# Breakout.net
KiCad netlist of a schematic drawn in EAGLE
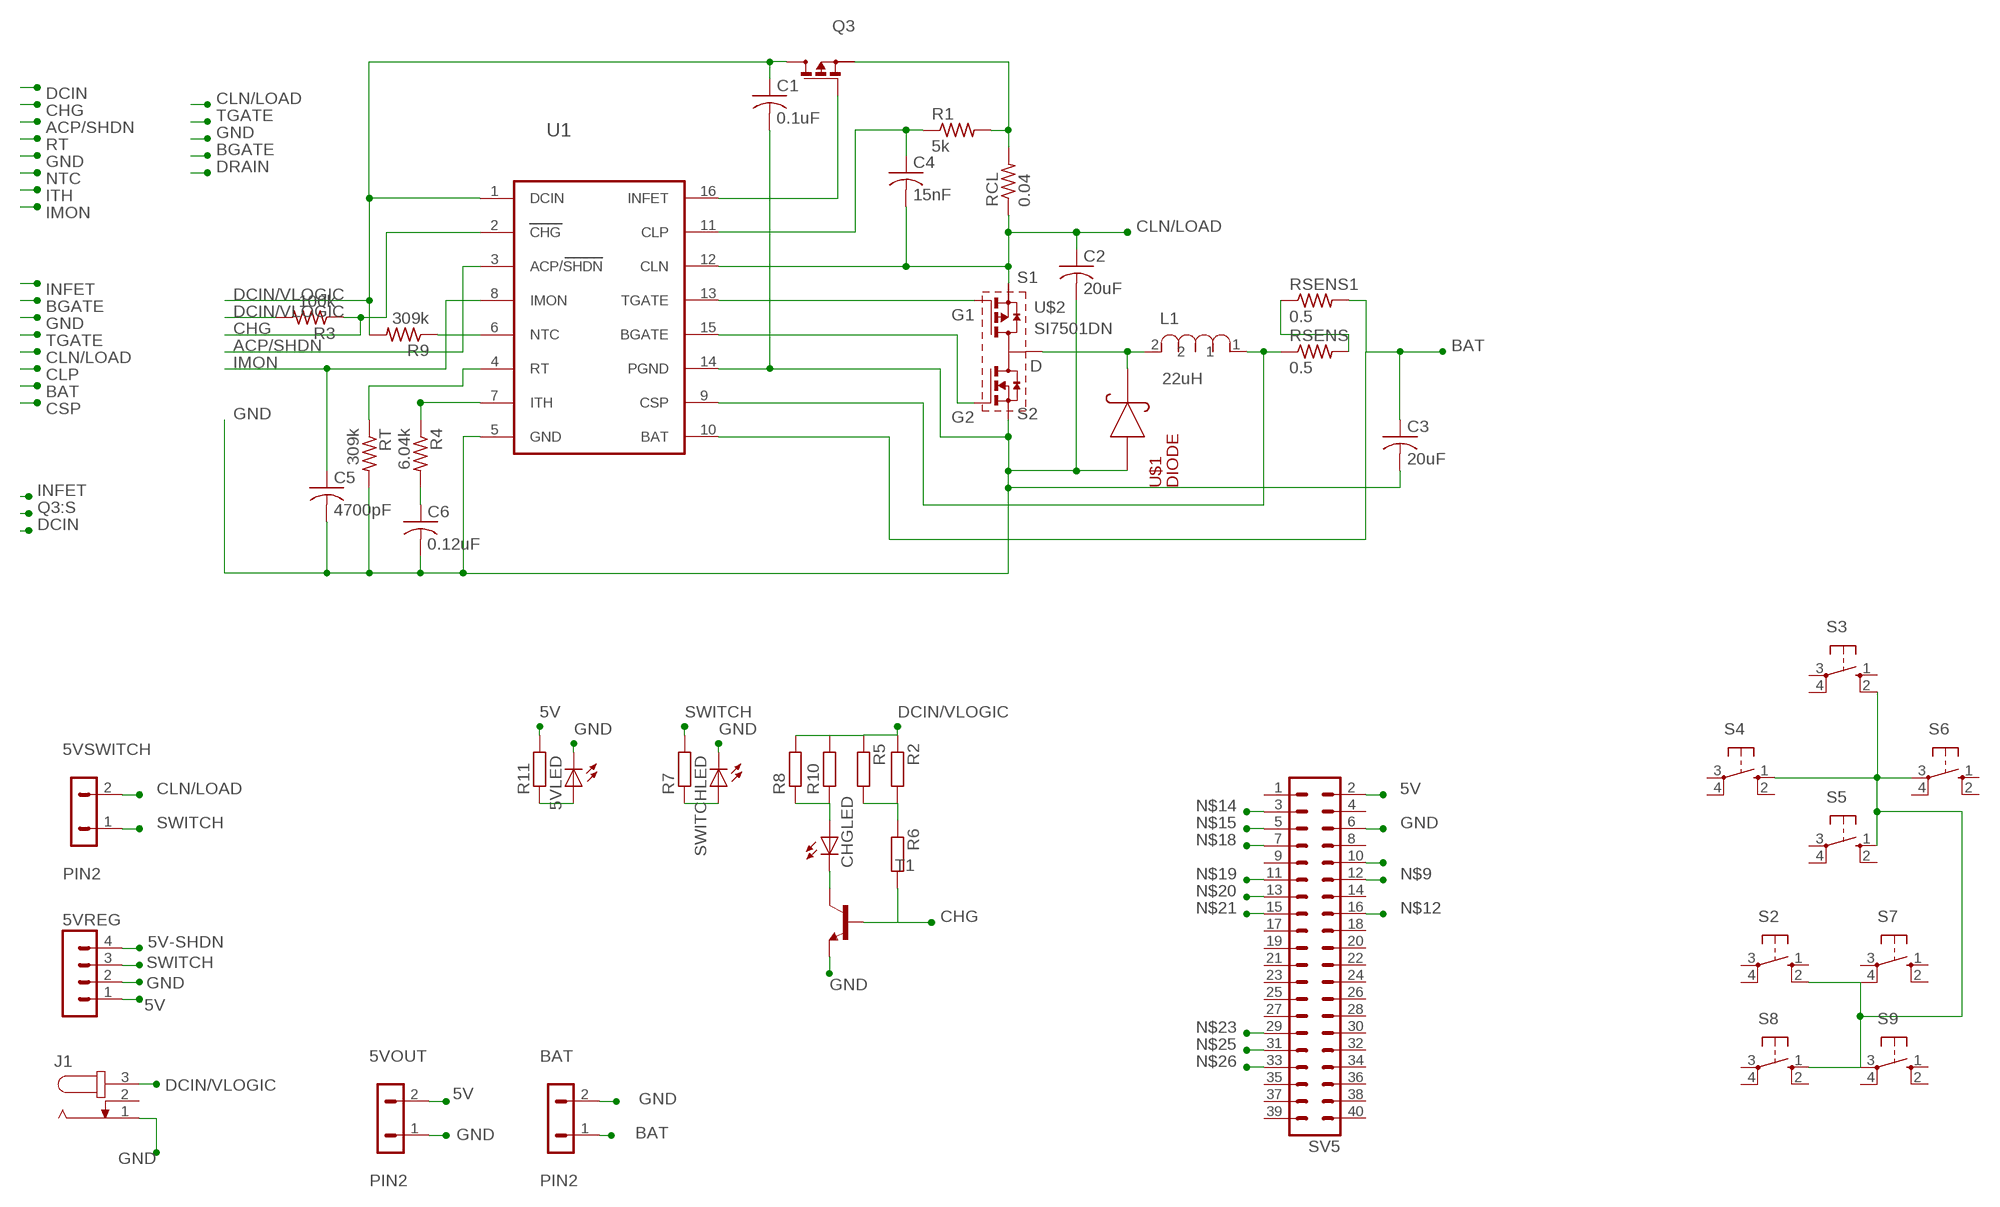
[diagram p0: schematic, sheet 1]

(export (version "E")
  (design (tool "Eeschema 10.0.6"))
  (components
    (comp (ref "5VLED")
      (value "LED5MM")
      (footprint "eagle-import:LED5MM")
      (libsource (lib "eagle-import") (part "LED5MM"))
    )
    (comp (ref "5VOUT")
      (value "PIN2")
      (footprint "eagle-import:PIN2")
      (libsource (lib "eagle-import") (part "PIN2"))
    )
    (comp (ref "5VREG")
      (value "MA04-1")
      (footprint "eagle-import:MA04-1")
      (libsource (lib "eagle-import") (part "MA04-1"))
    )
    (comp (ref "5VSWITCH")
      (value "PIN2")
      (footprint "eagle-import:PIN2")
      (libsource (lib "eagle-import") (part "PIN2"))
    )
    (comp (ref "BAT")
      (value "PIN2")
      (footprint "eagle-import:PIN2")
      (libsource (lib "eagle-import") (part "PIN2"))
    )
    (comp (ref "C1")
      (value "0.1uF")
      (footprint "eagle-import:C1210")
      (libsource (lib "eagle-import") (part "C-USC1210"))
    )
    (comp (ref "C2")
      (value "20uF")
      (footprint "eagle-import:C1210")
      (libsource (lib "eagle-import") (part "C-USC1210"))
    )
    (comp (ref "C3")
      (value "20uF")
      (footprint "eagle-import:C1210")
      (libsource (lib "eagle-import") (part "C-USC1210"))
    )
    (comp (ref "C4")
      (value "15nF")
      (footprint "eagle-import:C1210")
      (libsource (lib "eagle-import") (part "C-USC1210"))
    )
    (comp (ref "C5")
      (value "4700pF")
      (footprint "eagle-import:C1210")
      (libsource (lib "eagle-import") (part "C-USC1210"))
    )
    (comp (ref "C6")
      (value "0.12uF")
      (footprint "eagle-import:C1210")
      (libsource (lib "eagle-import") (part "C-USC1210"))
    )
    (comp (ref "CHGLED")
      (value "LED5MM")
      (footprint "eagle-import:LED5MM")
      (libsource (lib "eagle-import") (part "LED5MM"))
    )
    (comp (ref "J1")
      (value "JACK-PLUG0")
      (footprint "eagle-import:SPC4077")
      (libsource (lib "eagle-import") (part "JACK-PLUG0"))
    )
    (comp (ref "L1")
      (value "22uH")
      (footprint "eagle-import:POWERINDUCTOR")
      (libsource (lib "eagle-import") (part "SDR1005INDUCTOR"))
    )
    (comp (ref "Q3")
      (value "MOSFET")
      (footprint "eagle-import:SOT-23")
      (libsource (lib "eagle-import") (part "MOSFET"))
    )
    (comp (ref "R1")
      (value "5k")
      (footprint "eagle-import:R1206")
      (libsource (lib "eagle-import") (part "R-US_R1206"))
    )
    (comp (ref "R2")
      (value "R-EU_0207/7")
      (footprint "eagle-import:0207_7")
      (libsource (lib "eagle-import") (part "R-EU_0207/7"))
    )
    (comp (ref "R3")
      (value "100k")
      (footprint "eagle-import:R1206")
      (libsource (lib "eagle-import") (part "R-US_R1206"))
    )
    (comp (ref "R4")
      (value "6.04k")
      (footprint "eagle-import:R1206")
      (libsource (lib "eagle-import") (part "R-US_R1206"))
    )
    (comp (ref "R5")
      (value "R-EU_0207/7")
      (footprint "eagle-import:0207_7")
      (libsource (lib "eagle-import") (part "R-EU_0207/7"))
    )
    (comp (ref "R6")
      (value "R-EU_0207/7")
      (footprint "eagle-import:0207_7")
      (libsource (lib "eagle-import") (part "R-EU_0207/7"))
    )
    (comp (ref "R7")
      (value "R-EU_0207/7")
      (footprint "eagle-import:0207_7")
      (libsource (lib "eagle-import") (part "R-EU_0207/7"))
    )
    (comp (ref "R8")
      (value "R-EU_0207/7")
      (footprint "eagle-import:0207_7")
      (libsource (lib "eagle-import") (part "R-EU_0207/7"))
    )
    (comp (ref "R9")
      (value "309k")
      (footprint "eagle-import:R1206")
      (libsource (lib "eagle-import") (part "R-US_R1206"))
    )
    (comp (ref "R10")
      (value "R-EU_0207/7")
      (footprint "eagle-import:0207_7")
      (libsource (lib "eagle-import") (part "R-EU_0207/7"))
    )
    (comp (ref "R11")
      (value "R-EU_0207/7")
      (footprint "eagle-import:0207_7")
      (libsource (lib "eagle-import") (part "R-EU_0207/7"))
    )
    (comp (ref "RCL")
      (value "0.04")
      (footprint "eagle-import:R1206")
      (libsource (lib "eagle-import") (part "R-US_R1206"))
    )
    (comp (ref "RSENS")
      (value "0.5")
      (footprint "eagle-import:0612_1632")
      (libsource (lib "eagle-import") (part "0612/1632"))
    )
    (comp (ref "RSENS1")
      (value "0.5")
      (footprint "eagle-import:0612_1632")
      (libsource (lib "eagle-import") (part "0612/1632"))
    )
    (comp (ref "RT")
      (value "309k")
      (footprint "eagle-import:R1206")
      (libsource (lib "eagle-import") (part "R-US_R1206"))
    )
    (comp (ref "S2")
      (value "10-XX")
      (footprint "eagle-import:B3F-10XX")
      (fields (field (name "MPN") "B3F-1000"))
      (libsource (lib "eagle-import") (part "10-XX"))
    )
    (comp (ref "S3")
      (value "10-XX")
      (footprint "eagle-import:B3F-10XX")
      (fields (field (name "MPN") "B3F-1000"))
      (libsource (lib "eagle-import") (part "10-XX"))
    )
    (comp (ref "S4")
      (value "10-XX")
      (footprint "eagle-import:B3F-10XX")
      (fields (field (name "MPN") "B3F-1000"))
      (libsource (lib "eagle-import") (part "10-XX"))
    )
    (comp (ref "S5")
      (value "10-XX")
      (footprint "eagle-import:B3F-10XX")
      (fields (field (name "MPN") "B3F-1000"))
      (libsource (lib "eagle-import") (part "10-XX"))
    )
    (comp (ref "S6")
      (value "10-XX")
      (footprint "eagle-import:B3F-10XX")
      (fields (field (name "MPN") "B3F-1000"))
      (libsource (lib "eagle-import") (part "10-XX"))
    )
    (comp (ref "S7")
      (value "10-XX")
      (footprint "eagle-import:B3F-10XX")
      (fields (field (name "MPN") "B3F-1000"))
      (libsource (lib "eagle-import") (part "10-XX"))
    )
    (comp (ref "S8")
      (value "10-XX")
      (footprint "eagle-import:B3F-10XX")
      (fields (field (name "MPN") "B3F-1000"))
      (libsource (lib "eagle-import") (part "10-XX"))
    )
    (comp (ref "S9")
      (value "10-XX")
      (footprint "eagle-import:B3F-10XX")
      (fields (field (name "MPN") "B3F-1000"))
      (libsource (lib "eagle-import") (part "10-XX"))
    )
    (comp (ref "SV5")
      (value "MA20-2")
      (footprint "eagle-import:MA20-2")
      (libsource (lib "eagle-import") (part "MA20-2"))
    )
    (comp (ref "SWITCHLED")
      (value "LED5MM")
      (footprint "eagle-import:LED5MM")
      (libsource (lib "eagle-import") (part "LED5MM"))
    )
    (comp (ref "T1")
      (value "-NPN-TO92-E1")
      (footprint "eagle-import:TO92-E1")
      (libsource (lib "eagle-import") (part "-NPN-TO92-E1"))
    )
    (comp (ref "U$1")
      (value "DIODE")
      (footprint "eagle-import:DIODE")
      (libsource (lib "eagle-import") (part "DIODE"))
    )
    (comp (ref "U$2")
      (value "SI7501DN")
      (footprint "eagle-import:POWERPAK")
      (libsource (lib "eagle-import") (part "SI7501DN"))
    )
    (comp (ref "U1")
      (value "LTC6004")
      (footprint "eagle-import:SSOP-16")
      (libsource (lib "eagle-import") (part "LTC6004"))
    )
  )
  (nets
    (net (code "1") (name "/5V") (class "Default")
      (node (ref "5VOUT") (pin "2") (pinfunction "2_2") (pintype "passive"))
      (node (ref "5VREG") (pin "1") (pinfunction "1_1") (pintype "passive"))
      (node (ref "R11") (pin "2") (pinfunction "2_2") (pintype "passive"))
      (node (ref "SV5") (pin "2") (pinfunction "2_2") (pintype "passive"))
    )
    (net (code "2") (name "/5V-SHDN") (class "Default")
      (node (ref "5VREG") (pin "4") (pinfunction "4_4") (pintype "passive"))
    )
    (net (code "3") (name "/ACP{slash}SHDN") (class "Default")
      (node (ref "U1") (pin "3") (pinfunction "ACP/SHDN_3") (pintype "power_in"))
    )
    (net (code "4") (name "/BAT") (class "Default")
      (node (ref "BAT") (pin "1") (pinfunction "1_1") (pintype "passive"))
      (node (ref "C3") (pin "1") (pinfunction "1_1") (pintype "passive"))
      (node (ref "RSENS1") (pin "2") (pinfunction "2_2") (pintype "passive"))
      (node (ref "U1") (pin "10") (pinfunction "BAT_10") (pintype "power_in"))
    )
    (net (code "5") (name "/BGATE") (class "Default")
      (node (ref "U$2") (pin "G2") (pinfunction "G2_G2") (pintype "passive"))
      (node (ref "U1") (pin "15") (pinfunction "BGATE_15") (pintype "power_in"))
    )
    (net (code "6") (name "/CHG") (class "Default")
      (node (ref "R3") (pin "1") (pinfunction "1_1") (pintype "passive"))
      (node (ref "R6") (pin "2") (pinfunction "2_2") (pintype "passive"))
      (node (ref "T1") (pin "2") (pinfunction "B_2") (pintype "passive"))
      (node (ref "U1") (pin "2") (pinfunction "CHG_2") (pintype "power_in"))
    )
    (net (code "7") (name "/CLN{slash}LOAD") (class "Default")
      (node (ref "5VSWITCH") (pin "2") (pinfunction "2_2") (pintype "passive"))
      (node (ref "C2") (pin "1") (pinfunction "1_1") (pintype "passive"))
      (node (ref "C4") (pin "2") (pinfunction "2_2") (pintype "passive"))
      (node (ref "RCL") (pin "1") (pinfunction "1_1") (pintype "passive"))
      (node (ref "U$2") (pin "S1") (pinfunction "S1_S1") (pintype "passive"))
      (node (ref "U1") (pin "12") (pinfunction "CLN_12") (pintype "power_in"))
    )
    (net (code "8") (name "/CLP") (class "Default")
      (node (ref "C4") (pin "1") (pinfunction "1_1") (pintype "passive"))
      (node (ref "R1") (pin "1") (pinfunction "1_1") (pintype "passive"))
      (node (ref "U1") (pin "11") (pinfunction "CLP_11") (pintype "output"))
    )
    (net (code "9") (name "/CSP") (class "Default")
      (node (ref "L1") (pin "1") (pinfunction "1_1") (pintype "passive"))
      (node (ref "RSENS") (pin "1") (pinfunction "1_1") (pintype "passive"))
      (node (ref "U1") (pin "9") (pinfunction "CSP_9") (pintype "power_in"))
    )
    (net (code "11") (name "/DCIN{slash}VLOGIC") (class "Default")
      (node (ref "C1") (pin "1") (pinfunction "1_1") (pintype "passive"))
      (node (ref "J1") (pin "3") (pinfunction "3_3") (pintype "passive"))
      (node (ref "Q3") (pin "DRAIN") (pinfunction "D_DRAIN") (pintype "passive"))
      (node (ref "R10") (pin "2") (pinfunction "2_2") (pintype "passive"))
      (node (ref "R2") (pin "1") (pinfunction "1_1") (pintype "passive"))
      (node (ref "R3") (pin "2") (pinfunction "2_2") (pintype "passive"))
      (node (ref "R5") (pin "1") (pinfunction "1_1") (pintype "passive"))
      (node (ref "R8") (pin "2") (pinfunction "2_2") (pintype "passive"))
      (node (ref "R9") (pin "2") (pinfunction "2_2") (pintype "passive"))
      (node (ref "U1") (pin "1") (pinfunction "DCIN_1") (pintype "power_in"))
    )
    (net (code "12") (name "/DRAIN") (class "Default")
      (node (ref "L1") (pin "2") (pinfunction "2_2") (pintype "passive"))
      (node (ref "U$1") (pin "P$1") (pinfunction "2_P$1") (pintype "bidirectional"))
      (node (ref "U$2") (pin "D") (pinfunction "D_D") (pintype "passive"))
    )
    (net (code "13") (name "/GND") (class "Default")
      (node (ref "5VLED") (pin "K") (pinfunction "C_K") (pintype "passive"))
      (node (ref "5VOUT") (pin "1") (pinfunction "1_1") (pintype "passive"))
      (node (ref "5VREG") (pin "2") (pinfunction "2_2") (pintype "passive"))
      (node (ref "BAT") (pin "2") (pinfunction "2_2") (pintype "passive"))
      (node (ref "C1") (pin "2") (pinfunction "2_2") (pintype "passive"))
      (node (ref "C2") (pin "2") (pinfunction "2_2") (pintype "passive"))
      (node (ref "C3") (pin "2") (pinfunction "2_2") (pintype "passive"))
      (node (ref "C5") (pin "2") (pinfunction "2_2") (pintype "passive"))
      (node (ref "C6") (pin "2") (pinfunction "2_2") (pintype "passive"))
      (node (ref "J1") (pin "1") (pinfunction "1_1") (pintype "passive"))
      (node (ref "RT") (pin "2") (pinfunction "2_2") (pintype "passive"))
      (node (ref "S2") (pin "2") (pinfunction "S1_2") (pintype "passive"))
      (node (ref "S3") (pin "2") (pinfunction "S1_2") (pintype "passive"))
      (node (ref "S4") (pin "1") (pinfunction "S_1") (pintype "passive"))
      (node (ref "S5") (pin "1") (pinfunction "S_1") (pintype "passive"))
      (node (ref "S6") (pin "3") (pinfunction "P_3") (pintype "passive"))
      (node (ref "S7") (pin "4") (pinfunction "P1_4") (pintype "passive"))
      (node (ref "S8") (pin "1") (pinfunction "S_1") (pintype "passive"))
      (node (ref "S9") (pin "3") (pinfunction "P_3") (pintype "passive"))
      (node (ref "SV5") (pin "6") (pinfunction "6_6") (pintype "passive"))
      (node (ref "SWITCHLED") (pin "K") (pinfunction "C_K") (pintype "passive"))
      (node (ref "T1") (pin "3") (pinfunction "E_3") (pintype "passive"))
      (node (ref "U$1") (pin "P$2") (pinfunction "1_P$2") (pintype "bidirectional"))
      (node (ref "U$2") (pin "S2") (pinfunction "S2_S2") (pintype "passive"))
      (node (ref "U1") (pin "14") (pinfunction "PGND_14") (pintype "power_in"))
      (node (ref "U1") (pin "5") (pinfunction "GND_5") (pintype "input"))
    )
    (net (code "14") (name "/IMON") (class "Default")
      (node (ref "C5") (pin "1") (pinfunction "1_1") (pintype "passive"))
      (node (ref "U1") (pin "8") (pinfunction "IMON_8") (pintype "power_in"))
    )
    (net (code "15") (name "/INFET") (class "Default")
      (node (ref "Q3") (pin "GATE") (pinfunction "G_GATE") (pintype "passive"))
      (node (ref "U1") (pin "16") (pinfunction "INFET_16") (pintype "output"))
    )
    (net (code "16") (name "/ITH") (class "Default")
      (node (ref "R4") (pin "1") (pinfunction "1_1") (pintype "passive"))
      (node (ref "U1") (pin "7") (pinfunction "ITH_7") (pintype "input"))
    )
    (net (code "17") (name "/N$9") (class "Default")
      (node (ref "SV5") (pin "12") (pinfunction "12_12") (pintype "passive"))
    )
    (net (code "18") (name "/N$12") (class "Default")
      (node (ref "SV5") (pin "16") (pinfunction "16_16") (pintype "passive"))
    )
    (net (code "19") (name "/N$14") (class "Default")
      (node (ref "SV5") (pin "3") (pinfunction "3_3") (pintype "passive"))
    )
    (net (code "20") (name "/N$15") (class "Default")
      (node (ref "SV5") (pin "5") (pinfunction "5_5") (pintype "passive"))
    )
    (net (code "21") (name "/N$18") (class "Default")
      (node (ref "SV5") (pin "7") (pinfunction "7_7") (pintype "passive"))
    )
    (net (code "22") (name "/N$19") (class "Default")
      (node (ref "SV5") (pin "11") (pinfunction "11_11") (pintype "passive"))
    )
    (net (code "23") (name "/N$20") (class "Default")
      (node (ref "SV5") (pin "13") (pinfunction "13_13") (pintype "passive"))
    )
    (net (code "24") (name "/N$21") (class "Default")
      (node (ref "SV5") (pin "15") (pinfunction "15_15") (pintype "passive"))
    )
    (net (code "25") (name "/N$23") (class "Default")
      (node (ref "SV5") (pin "29") (pinfunction "29_29") (pintype "passive"))
    )
    (net (code "26") (name "/N$25") (class "Default")
      (node (ref "SV5") (pin "31") (pinfunction "31_31") (pintype "passive"))
    )
    (net (code "27") (name "/N$26") (class "Default")
      (node (ref "SV5") (pin "33") (pinfunction "33_33") (pintype "passive"))
    )
    (net (code "28") (name "/NTC") (class "Default")
      (node (ref "R9") (pin "1") (pinfunction "1_1") (pintype "passive"))
      (node (ref "U1") (pin "6") (pinfunction "NTC_6") (pintype "power_in"))
    )
    (net (code "29") (name "/Q3:S") (class "Default")
      (node (ref "Q3") (pin "SOURCE") (pinfunction "S_SOURCE") (pintype "passive"))
      (node (ref "R1") (pin "2") (pinfunction "2_2") (pintype "passive"))
      (node (ref "RCL") (pin "2") (pinfunction "2_2") (pintype "passive"))
    )
    (net (code "30") (name "/RT") (class "Default")
      (node (ref "RT") (pin "1") (pinfunction "1_1") (pintype "passive"))
      (node (ref "U1") (pin "4") (pinfunction "RT_4") (pintype "input"))
    )
    (net (code "31") (name "/SWITCH") (class "Default")
      (node (ref "5VREG") (pin "3") (pinfunction "3_3") (pintype "passive"))
      (node (ref "5VSWITCH") (pin "1") (pinfunction "1_1") (pintype "passive"))
      (node (ref "R7") (pin "2") (pinfunction "2_2") (pintype "passive"))
    )
    (net (code "32") (name "/TGATE") (class "Default")
      (node (ref "U$2") (pin "G1") (pinfunction "G1_G1") (pintype "passive"))
      (node (ref "U1") (pin "13") (pinfunction "TGATE_13") (pintype "input"))
    )
    (net (code "33") (name "Net-(5VLED-PadA)") (class "Default")
      (node (ref "5VLED") (pin "A") (pinfunction "A_A") (pintype "passive"))
      (node (ref "R11") (pin "1") (pinfunction "1_1") (pintype "passive"))
    )
    (net (code "34") (name "Net-(C6-Pad1)") (class "Default")
      (node (ref "C6") (pin "1") (pinfunction "1_1") (pintype "passive"))
      (node (ref "R4") (pin "2") (pinfunction "2_2") (pintype "passive"))
    )
    (net (code "35") (name "Net-(CHGLED-C)") (class "Default")
      (node (ref "CHGLED") (pin "K") (pinfunction "C_K") (pintype "passive"))
      (node (ref "T1") (pin "1") (pinfunction "C_1") (pintype "passive"))
    )
    (net (code "36") (name "Net-(CHGLED-PadA)") (class "Default")
      (node (ref "CHGLED") (pin "A") (pinfunction "A_A") (pintype "passive"))
      (node (ref "R10") (pin "1") (pinfunction "1_1") (pintype "passive"))
      (node (ref "R8") (pin "1") (pinfunction "1_1") (pintype "passive"))
    )
    (net (code "37") (name "Net-(R2-Pad2)") (class "Default")
      (node (ref "R2") (pin "2") (pinfunction "2_2") (pintype "passive"))
      (node (ref "R5") (pin "2") (pinfunction "2_2") (pintype "passive"))
      (node (ref "R6") (pin "1") (pinfunction "1_1") (pintype "passive"))
    )
    (net (code "38") (name "Net-(R7-Pad1)") (class "Default")
      (node (ref "R7") (pin "1") (pinfunction "1_1") (pintype "passive"))
      (node (ref "SWITCHLED") (pin "A") (pinfunction "A_A") (pintype "passive"))
    )
    (net (code "39") (name "Net-(RSENS-Pad2)") (class "Default")
      (node (ref "RSENS") (pin "2") (pinfunction "2_2") (pintype "passive"))
      (node (ref "RSENS1") (pin "1") (pinfunction "1_1") (pintype "passive"))
    )
    (net (code "40") (name "unconnected-(J1-Pad2)") (class "Default")
      (node (ref "J1") (pin "2") (pinfunction "2_2") (pintype "passive"))
    )
    (net (code "41") (name "unconnected-(S2-P-Pad3)") (class "Default")
      (node (ref "S2") (pin "3") (pinfunction "P_3") (pintype "passive"))
    )
    (net (code "42") (name "unconnected-(S2-P1-Pad4)") (class "Default")
      (node (ref "S2") (pin "4") (pinfunction "P1_4") (pintype "passive"))
    )
    (net (code "43") (name "unconnected-(S2-S-Pad1)") (class "Default")
      (node (ref "S2") (pin "1") (pinfunction "S_1") (pintype "passive"))
    )
    (net (code "44") (name "unconnected-(S3-P-Pad3)") (class "Default")
      (node (ref "S3") (pin "3") (pinfunction "P_3") (pintype "passive"))
    )
    (net (code "45") (name "unconnected-(S3-P1-Pad4)") (class "Default")
      (node (ref "S3") (pin "4") (pinfunction "P1_4") (pintype "passive"))
    )
    (net (code "46") (name "unconnected-(S3-S-Pad1)") (class "Default")
      (node (ref "S3") (pin "1") (pinfunction "S_1") (pintype "passive"))
    )
    (net (code "47") (name "unconnected-(S4-P-Pad3)") (class "Default")
      (node (ref "S4") (pin "3") (pinfunction "P_3") (pintype "passive"))
    )
    (net (code "48") (name "unconnected-(S4-P1-Pad4)") (class "Default")
      (node (ref "S4") (pin "4") (pinfunction "P1_4") (pintype "passive"))
    )
    (net (code "49") (name "unconnected-(S4-S1-Pad2)") (class "Default")
      (node (ref "S4") (pin "2") (pinfunction "S1_2") (pintype "passive"))
    )
    (net (code "50") (name "unconnected-(S5-P-Pad3)") (class "Default")
      (node (ref "S5") (pin "3") (pinfunction "P_3") (pintype "passive"))
    )
    (net (code "51") (name "unconnected-(S5-P1-Pad4)") (class "Default")
      (node (ref "S5") (pin "4") (pinfunction "P1_4") (pintype "passive"))
    )
    (net (code "52") (name "unconnected-(S5-S1-Pad2)") (class "Default")
      (node (ref "S5") (pin "2") (pinfunction "S1_2") (pintype "passive"))
    )
    (net (code "53") (name "unconnected-(S6-P1-Pad4)") (class "Default")
      (node (ref "S6") (pin "4") (pinfunction "P1_4") (pintype "passive"))
    )
    (net (code "54") (name "unconnected-(S6-S-Pad1)") (class "Default")
      (node (ref "S6") (pin "1") (pinfunction "S_1") (pintype "passive"))
    )
    (net (code "55") (name "unconnected-(S6-S1-Pad2)") (class "Default")
      (node (ref "S6") (pin "2") (pinfunction "S1_2") (pintype "passive"))
    )
    (net (code "56") (name "unconnected-(S7-P-Pad3)") (class "Default")
      (node (ref "S7") (pin "3") (pinfunction "P_3") (pintype "passive"))
    )
    (net (code "57") (name "unconnected-(S7-S-Pad1)") (class "Default")
      (node (ref "S7") (pin "1") (pinfunction "S_1") (pintype "passive"))
    )
    (net (code "58") (name "unconnected-(S7-S1-Pad2)") (class "Default")
      (node (ref "S7") (pin "2") (pinfunction "S1_2") (pintype "passive"))
    )
    (net (code "59") (name "unconnected-(S8-P-Pad3)") (class "Default")
      (node (ref "S8") (pin "3") (pinfunction "P_3") (pintype "passive"))
    )
    (net (code "60") (name "unconnected-(S8-P1-Pad4)") (class "Default")
      (node (ref "S8") (pin "4") (pinfunction "P1_4") (pintype "passive"))
    )
    (net (code "61") (name "unconnected-(S8-S1-Pad2)") (class "Default")
      (node (ref "S8") (pin "2") (pinfunction "S1_2") (pintype "passive"))
    )
    (net (code "62") (name "unconnected-(S9-P1-Pad4)") (class "Default")
      (node (ref "S9") (pin "4") (pinfunction "P1_4") (pintype "passive"))
    )
    (net (code "63") (name "unconnected-(S9-S-Pad1)") (class "Default")
      (node (ref "S9") (pin "1") (pinfunction "S_1") (pintype "passive"))
    )
    (net (code "64") (name "unconnected-(S9-S1-Pad2)") (class "Default")
      (node (ref "S9") (pin "2") (pinfunction "S1_2") (pintype "passive"))
    )
    (net (code "65") (name "unconnected-(SV5-Pad1)") (class "Default")
      (node (ref "SV5") (pin "1") (pinfunction "1_1") (pintype "passive"))
    )
    (net (code "66") (name "unconnected-(SV5-Pad4)") (class "Default")
      (node (ref "SV5") (pin "4") (pinfunction "4_4") (pintype "passive"))
    )
    (net (code "67") (name "unconnected-(SV5-Pad8)") (class "Default")
      (node (ref "SV5") (pin "8") (pinfunction "8_8") (pintype "passive"))
    )
    (net (code "68") (name "unconnected-(SV5-Pad9)") (class "Default")
      (node (ref "SV5") (pin "9") (pinfunction "9_9") (pintype "passive"))
    )
    (net (code "69") (name "unconnected-(SV5-Pad10)") (class "Default")
      (node (ref "SV5") (pin "10") (pinfunction "10_10") (pintype "passive"))
    )
    (net (code "70") (name "unconnected-(SV5-Pad14)") (class "Default")
      (node (ref "SV5") (pin "14") (pinfunction "14_14") (pintype "passive"))
    )
    (net (code "71") (name "unconnected-(SV5-Pad17)") (class "Default")
      (node (ref "SV5") (pin "17") (pinfunction "17_17") (pintype "passive"))
    )
    (net (code "72") (name "unconnected-(SV5-Pad18)") (class "Default")
      (node (ref "SV5") (pin "18") (pinfunction "18_18") (pintype "passive"))
    )
    (net (code "73") (name "unconnected-(SV5-Pad19)") (class "Default")
      (node (ref "SV5") (pin "19") (pinfunction "19_19") (pintype "passive"))
    )
    (net (code "74") (name "unconnected-(SV5-Pad20)") (class "Default")
      (node (ref "SV5") (pin "20") (pinfunction "20_20") (pintype "passive"))
    )
    (net (code "75") (name "unconnected-(SV5-Pad21)") (class "Default")
      (node (ref "SV5") (pin "21") (pinfunction "21_21") (pintype "passive"))
    )
    (net (code "76") (name "unconnected-(SV5-Pad22)") (class "Default")
      (node (ref "SV5") (pin "22") (pinfunction "22_22") (pintype "passive"))
    )
    (net (code "77") (name "unconnected-(SV5-Pad23)") (class "Default")
      (node (ref "SV5") (pin "23") (pinfunction "23_23") (pintype "passive"))
    )
    (net (code "78") (name "unconnected-(SV5-Pad24)") (class "Default")
      (node (ref "SV5") (pin "24") (pinfunction "24_24") (pintype "passive"))
    )
    (net (code "79") (name "unconnected-(SV5-Pad25)") (class "Default")
      (node (ref "SV5") (pin "25") (pinfunction "25_25") (pintype "passive"))
    )
    (net (code "80") (name "unconnected-(SV5-Pad26)") (class "Default")
      (node (ref "SV5") (pin "26") (pinfunction "26_26") (pintype "passive"))
    )
    (net (code "81") (name "unconnected-(SV5-Pad27)") (class "Default")
      (node (ref "SV5") (pin "27") (pinfunction "27_27") (pintype "passive"))
    )
    (net (code "82") (name "unconnected-(SV5-Pad28)") (class "Default")
      (node (ref "SV5") (pin "28") (pinfunction "28_28") (pintype "passive"))
    )
    (net (code "83") (name "unconnected-(SV5-Pad30)") (class "Default")
      (node (ref "SV5") (pin "30") (pinfunction "30_30") (pintype "passive"))
    )
    (net (code "84") (name "unconnected-(SV5-Pad32)") (class "Default")
      (node (ref "SV5") (pin "32") (pinfunction "32_32") (pintype "passive"))
    )
    (net (code "85") (name "unconnected-(SV5-Pad34)") (class "Default")
      (node (ref "SV5") (pin "34") (pinfunction "34_34") (pintype "passive"))
    )
    (net (code "86") (name "unconnected-(SV5-Pad35)") (class "Default")
      (node (ref "SV5") (pin "35") (pinfunction "35_35") (pintype "passive"))
    )
    (net (code "87") (name "unconnected-(SV5-Pad36)") (class "Default")
      (node (ref "SV5") (pin "36") (pinfunction "36_36") (pintype "passive"))
    )
    (net (code "88") (name "unconnected-(SV5-Pad37)") (class "Default")
      (node (ref "SV5") (pin "37") (pinfunction "37_37") (pintype "passive"))
    )
    (net (code "89") (name "unconnected-(SV5-Pad38)") (class "Default")
      (node (ref "SV5") (pin "38") (pinfunction "38_38") (pintype "passive"))
    )
    (net (code "90") (name "unconnected-(SV5-Pad39)") (class "Default")
      (node (ref "SV5") (pin "39") (pinfunction "39_39") (pintype "passive"))
    )
    (net (code "91") (name "unconnected-(SV5-Pad40)") (class "Default")
      (node (ref "SV5") (pin "40") (pinfunction "40_40") (pintype "passive"))
    )
  )
)
